# AzoreanReflowController.net
KiCad netlist of a schematic drawn in EAGLE
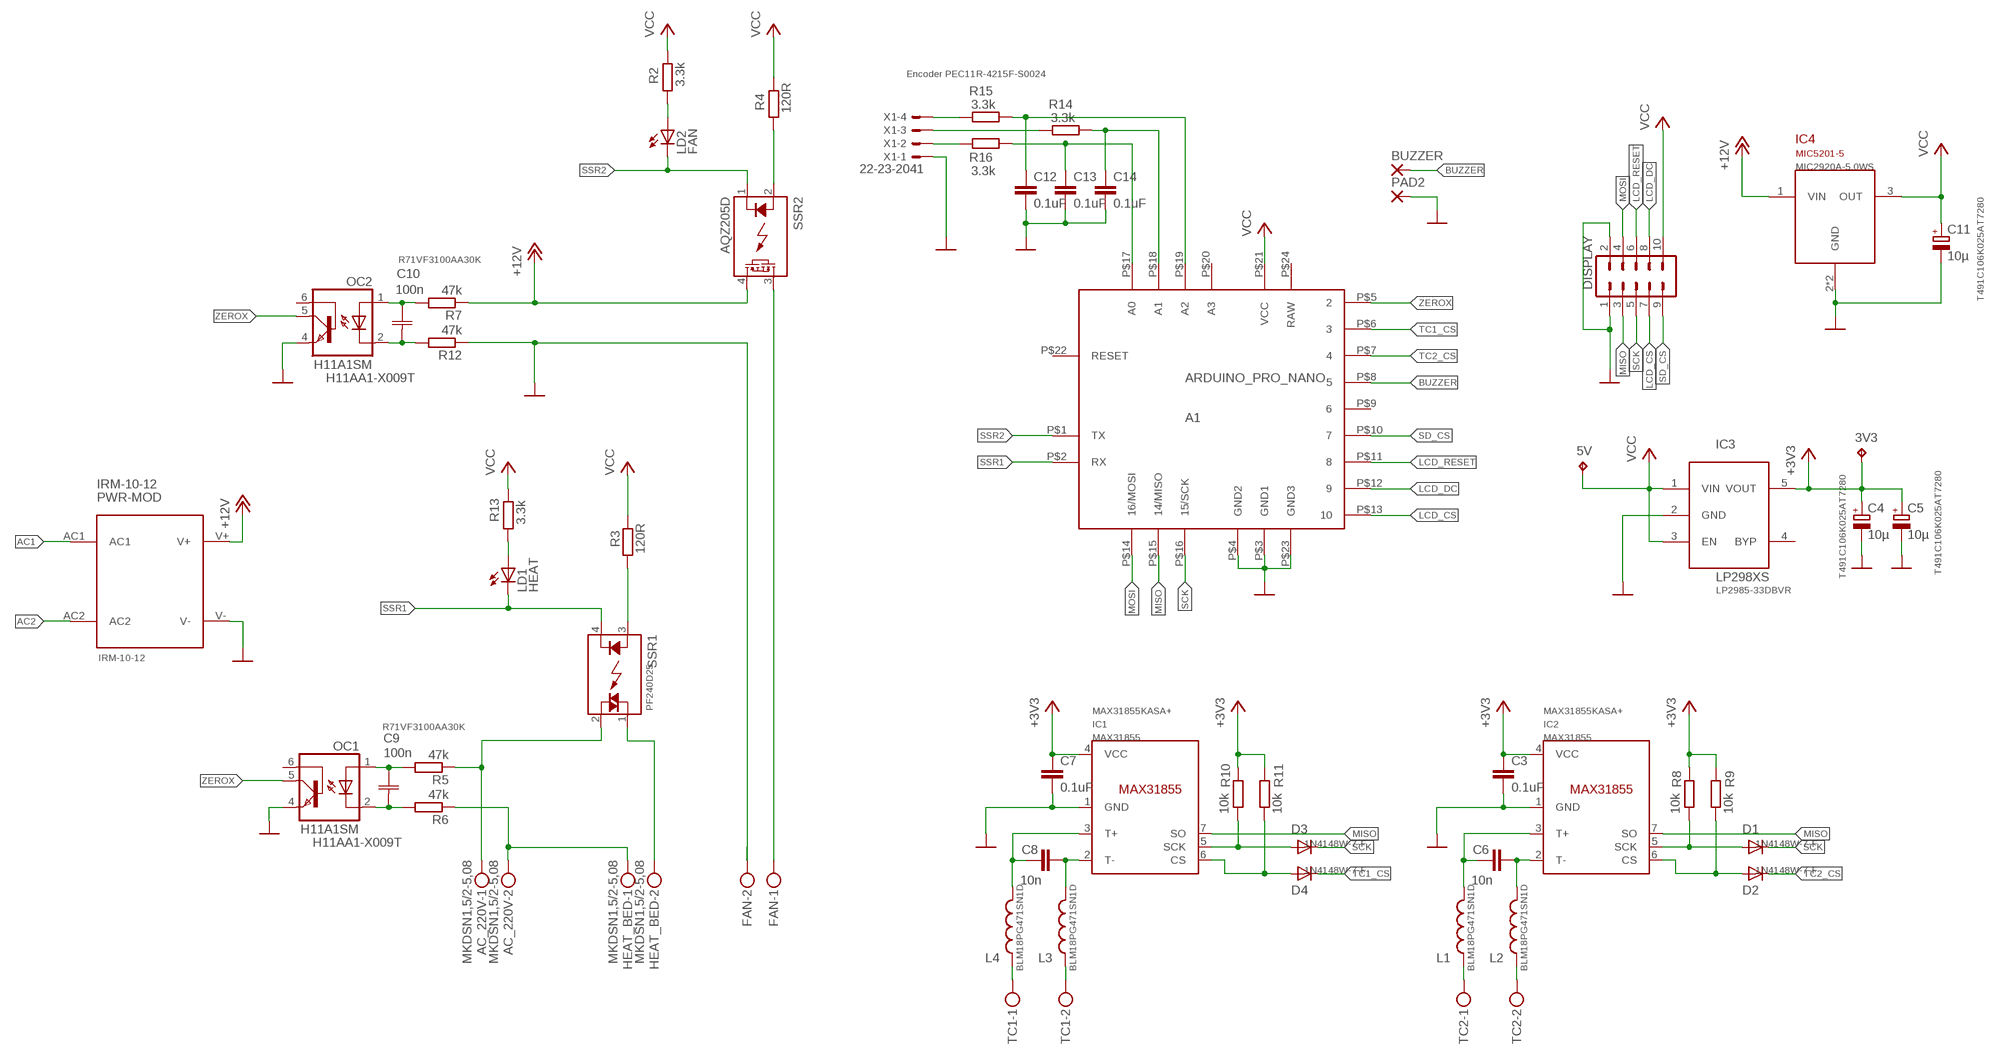
[diagram p0: schematic, sheet 1]

(export (version "E")
  (design (tool "Eeschema 10.0.6"))
  (components
    (comp (ref "3V3")
      (value "TPTP08R")
      (footprint "eagle-import:TP08R")
      (libsource (lib "eagle-import") (part "TPTP08R"))
    )
    (comp (ref "5V")
      (value "TPTP08R")
      (footprint "eagle-import:TP08R")
      (libsource (lib "eagle-import") (part "TPTP08R"))
    )
    (comp (ref "A1")
      (value "ARDUINO_PRO_NANO")
      (footprint "eagle-import:ARDUINO_PRO_NANO")
      (libsource (lib "eagle-import") (part "ARDUINO_PRO_NANO"))
    )
    (comp (ref "AC_220V")
      (value "MKDSN1,5/2-5,08")
      (footprint "eagle-import:MKDSN1,5_2-5,08")
      (fields (field (name "MPN") "MKDSN 1,5/2-5.08") (field (name "REF") "1715721 "))
      (libsource (lib "eagle-import") (part "MKDSN1,5/2-5,08"))
    )
    (comp (ref "BUZZER")
      (value "1,6/0,8")
      (footprint "eagle-import:1,6_0,8")
      (libsource (lib "eagle-import") (part "1,6/0,8"))
    )
    (comp (ref "C3")
      (value "0.1uF")
      (footprint "eagle-import:0603")
      (libsource (lib "eagle-import") (part "0.1UF-0603-25V-5%"))
    )
    (comp (ref "C4")
      (value "10µ")
      (footprint "eagle-import:C_6032-28R")
      (fields (field (name "REF") "T491C106K025AT7280"))
      (libsource (lib "eagle-import") (part "CPOL-EUC/6032-28R"))
    )
    (comp (ref "C5")
      (value "10µ")
      (footprint "eagle-import:C_6032-28R")
      (fields (field (name "REF") "T491C106K025AT7280"))
      (libsource (lib "eagle-import") (part "CPOL-EUC/6032-28R"))
    )
    (comp (ref "C6")
      (value "10n")
      (footprint "eagle-import:C0603")
      (libsource (lib "eagle-import") (part "C-EUC0603"))
    )
    (comp (ref "C7")
      (value "0.1uF")
      (footprint "eagle-import:0603")
      (libsource (lib "eagle-import") (part "0.1UF-0603-25V-5%"))
    )
    (comp (ref "C8")
      (value "10n")
      (footprint "eagle-import:C0603")
      (libsource (lib "eagle-import") (part "C-EUC0603"))
    )
    (comp (ref "C9")
      (value "100n")
      (footprint "eagle-import:R71V")
      (fields (field (name "REF") "R71VF3100AA30K"))
      (libsource (lib "eagle-import") (part "R71VF"))
    )
    (comp (ref "C10")
      (value "100n")
      (footprint "eagle-import:R71V")
      (fields (field (name "REF") "R71VF3100AA30K"))
      (libsource (lib "eagle-import") (part "R71VF"))
    )
    (comp (ref "C11")
      (value "10µ")
      (footprint "eagle-import:C_6032-28R")
      (fields (field (name "REF") "T491C106K025AT7280"))
      (libsource (lib "eagle-import") (part "CPOL-EUC/6032-28R"))
    )
    (comp (ref "C12")
      (value "0.1uF")
      (footprint "eagle-import:0603")
      (libsource (lib "eagle-import") (part "0.1UF-0603-25V-5%"))
    )
    (comp (ref "C13")
      (value "0.1uF")
      (footprint "eagle-import:0603")
      (libsource (lib "eagle-import") (part "0.1UF-0603-25V-5%"))
    )
    (comp (ref "C14")
      (value "0.1uF")
      (footprint "eagle-import:0603")
      (libsource (lib "eagle-import") (part "0.1UF-0603-25V-5%"))
    )
    (comp (ref "D1")
      (value "DIODESOD-123")
      (footprint "eagle-import:SOD-123")
      (fields (field (name "REF") "1N4148W-7-F"))
      (libsource (lib "eagle-import") (part "DIODESOD-123"))
    )
    (comp (ref "D2")
      (value "DIODESOD-123")
      (footprint "eagle-import:SOD-123")
      (fields (field (name "REF") "1N4148W-7-F"))
      (libsource (lib "eagle-import") (part "DIODESOD-123"))
    )
    (comp (ref "D3")
      (value "DIODESOD-123")
      (footprint "eagle-import:SOD-123")
      (fields (field (name "REF") "1N4148W-7-F"))
      (libsource (lib "eagle-import") (part "DIODESOD-123"))
    )
    (comp (ref "D4")
      (value "DIODESOD-123")
      (footprint "eagle-import:SOD-123")
      (fields (field (name "REF") "1N4148W-7-F"))
      (libsource (lib "eagle-import") (part "DIODESOD-123"))
    )
    (comp (ref "DISPLAY")
      (value "M05X2SHD-NS")
      (footprint "eagle-import:2X5-SHROUDED-NS")
      (libsource (lib "eagle-import") (part "M05X2SHD-NS"))
    )
    (comp (ref "FAN")
      (value "MKDSN1,5/2-5,08")
      (footprint "eagle-import:MKDSN1,5_2-5,08")
      (fields (field (name "MPN") "MKDSN 1,5/2-5.08") (field (name "REF") "1715721 "))
      (libsource (lib "eagle-import") (part "MKDSN1,5/2-5,08"))
    )
    (comp (ref "HEAT_BED")
      (value "MKDSN1,5/2-5,08")
      (footprint "eagle-import:MKDSN1,5_2-5,08")
      (fields (field (name "MPN") "MKDSN 1,5/2-5.08") (field (name "REF") "1715721 "))
      (libsource (lib "eagle-import") (part "MKDSN1,5/2-5,08"))
    )
    (comp (ref "IC1")
      (value "MAX31855")
      (footprint "eagle-import:SOIC8")
      (fields (field (name "REF") "MAX31855KASA+"))
      (libsource (lib "eagle-import") (part "MAX31855"))
    )
    (comp (ref "IC2")
      (value "MAX31855")
      (footprint "eagle-import:SOIC8")
      (fields (field (name "REF") "MAX31855KASA+"))
      (libsource (lib "eagle-import") (part "MAX31855"))
    )
    (comp (ref "IC3")
      (value "LP298XS")
      (footprint "eagle-import:SOT23-5L")
      (fields (field (name "REF") "LP2985-33DBVR"))
      (libsource (lib "eagle-import") (part "LP298XS"))
    )
    (comp (ref "IC4")
      (value "MIC5201-5")
      (footprint "eagle-import:SOT-223")
      (fields (field (name "REF") "MIC2920A-5.0WS"))
      (libsource (lib "eagle-import") (part "MIC5201-5"))
    )
    (comp (ref "L1")
      (value "INDUCTOR0603")
      (footprint "eagle-import:0603")
      (fields (field (name "REF") "BLM18PG471SN1D"))
      (libsource (lib "eagle-import") (part "INDUCTOR0603"))
    )
    (comp (ref "L2")
      (value "INDUCTOR0603")
      (footprint "eagle-import:0603")
      (fields (field (name "REF") "BLM18PG471SN1D"))
      (libsource (lib "eagle-import") (part "INDUCTOR0603"))
    )
    (comp (ref "L3")
      (value "INDUCTOR0603")
      (footprint "eagle-import:0603")
      (fields (field (name "REF") "BLM18PG471SN1D"))
      (libsource (lib "eagle-import") (part "INDUCTOR0603"))
    )
    (comp (ref "L4")
      (value "INDUCTOR0603")
      (footprint "eagle-import:0603")
      (fields (field (name "REF") "BLM18PG471SN1D"))
      (libsource (lib "eagle-import") (part "INDUCTOR0603"))
    )
    (comp (ref "LD1")
      (value "HEAT")
      (footprint "eagle-import:CHIP-LED0603")
      (libsource (lib "eagle-import") (part "LEDCHIP-LED0603"))
    )
    (comp (ref "LD2")
      (value "FAN")
      (footprint "eagle-import:CHIP-LED0603")
      (libsource (lib "eagle-import") (part "LEDCHIP-LED0603"))
    )
    (comp (ref "OC1")
      (value "H11A1SM")
      (footprint "eagle-import:DIL6-SMD")
      (fields (field (name "REF") "H11AA1-X009T"))
      (libsource (lib "eagle-import") (part "optocoupler_320_H11A?MS1"))
    )
    (comp (ref "OC2")
      (value "H11A1SM")
      (footprint "eagle-import:DIL6-SMD")
      (fields (field (name "REF") "H11AA1-X009T"))
      (libsource (lib "eagle-import") (part "H11A?MS1"))
    )
    (comp (ref "PAD2")
      (value "1,6/0,8")
      (footprint "eagle-import:1,6_0,8")
      (libsource (lib "eagle-import") (part "1,6/0,8"))
    )
    (comp (ref "PWR-MOD")
      (value "IRM-10-12")
      (footprint "eagle-import:IRM-10-12")
      (fields (field (name "REF") "IRM-10-12"))
      (libsource (lib "eagle-import") (part "IRM-10-12"))
    )
    (comp (ref "R2")
      (value "3.3k")
      (footprint "eagle-import:R0603")
      (libsource (lib "eagle-import") (part "R-EU_R0603"))
    )
    (comp (ref "R3")
      (value "120R")
      (footprint "eagle-import:R0603")
      (libsource (lib "eagle-import") (part "R-EU_R0603"))
    )
    (comp (ref "R4")
      (value "120R")
      (footprint "eagle-import:R0603")
      (libsource (lib "eagle-import") (part "R-EU_R0603"))
    )
    (comp (ref "R5")
      (value "47k")
      (footprint "eagle-import:0207_5V")
      (libsource (lib "eagle-import") (part "R-EU_0207/5V"))
    )
    (comp (ref "R6")
      (value "47k")
      (footprint "eagle-import:0207_5V")
      (libsource (lib "eagle-import") (part "R-EU_0207/5V"))
    )
    (comp (ref "R7")
      (value "47k")
      (footprint "eagle-import:0207_5V")
      (libsource (lib "eagle-import") (part "R-EU_0207/5V"))
    )
    (comp (ref "R8")
      (value "10k")
      (footprint "eagle-import:R0603")
      (libsource (lib "eagle-import") (part "R-EU_R0603"))
    )
    (comp (ref "R9")
      (value "10k")
      (footprint "eagle-import:R0603")
      (libsource (lib "eagle-import") (part "R-EU_R0603"))
    )
    (comp (ref "R10")
      (value "10k")
      (footprint "eagle-import:R0603")
      (libsource (lib "eagle-import") (part "R-EU_R0603"))
    )
    (comp (ref "R11")
      (value "10k")
      (footprint "eagle-import:R0603")
      (libsource (lib "eagle-import") (part "R-EU_R0603"))
    )
    (comp (ref "R12")
      (value "47k")
      (footprint "eagle-import:0207_5V")
      (libsource (lib "eagle-import") (part "R-EU_0207/5V"))
    )
    (comp (ref "R13")
      (value "3.3k")
      (footprint "eagle-import:R0603")
      (libsource (lib "eagle-import") (part "R-EU_R0603"))
    )
    (comp (ref "R14")
      (value "3.3k")
      (footprint "eagle-import:R0603")
      (libsource (lib "eagle-import") (part "R-EU_R0603"))
    )
    (comp (ref "R15")
      (value "3.3k")
      (footprint "eagle-import:R0603")
      (libsource (lib "eagle-import") (part "R-EU_R0603"))
    )
    (comp (ref "R16")
      (value "3.3k")
      (footprint "eagle-import:R0603")
      (libsource (lib "eagle-import") (part "R-EU_R0603"))
    )
    (comp (ref "SSR1")
      (value "PF240D25")
      (footprint "eagle-import:PF240XX")
      (fields (field (name "REF") "PF240D25"))
      (libsource (lib "eagle-import") (part "PF240D25"))
    )
    (comp (ref "SSR2")
      (value "AQZ205D")
      (footprint "eagle-import:AQZ-SIL04")
      (fields (field (name "MF") "AROMAT/ MATSUSHITA") (field (name "SPICEPREFIX") "K"))
      (libsource (lib "eagle-import") (part "AQZ20D5"))
    )
    (comp (ref "TC1")
      (value "MKDSN1,5/2-5,08")
      (footprint "eagle-import:MKDSN1,5_2-5,08")
      (fields (field (name "MPN") "MKDSN 1,5/2-5.08") (field (name "REF") "1715721 "))
      (libsource (lib "eagle-import") (part "MKDSN1,5/2-5,08"))
    )
    (comp (ref "TC2")
      (value "MKDSN1,5/2-5,08")
      (footprint "eagle-import:MKDSN1,5_2-5,08")
      (fields (field (name "MPN") "MKDSN 1,5/2-5.08") (field (name "REF") "1715721 "))
      (libsource (lib "eagle-import") (part "MKDSN1,5/2-5,08"))
    )
    (comp (ref "X1")
      (value "22-23-2041")
      (footprint "eagle-import:22-23-2041")
      (fields (field (name "MF") "MOLEX"))
      (libsource (lib "eagle-import") (part "22-23-2041"))
    )
  )
  (nets
    (net (code "1") (name "+3V3") (class "Default")
      (node (ref "3V3") (pin "TP") (pinfunction "TP_TP") (pintype "input"))
      (node (ref "C3") (pin "1") (pinfunction "1_1") (pintype "passive"))
      (node (ref "C4") (pin "+") (pinfunction "+_+") (pintype "passive"))
      (node (ref "C5") (pin "+") (pinfunction "+_+") (pintype "passive"))
      (node (ref "C7") (pin "1") (pinfunction "1_1") (pintype "passive"))
      (node (ref "IC1") (pin "4") (pinfunction "VCC_4") (pintype "power_in"))
      (node (ref "IC2") (pin "4") (pinfunction "VCC_4") (pintype "power_in"))
      (node (ref "IC3") (pin "5") (pinfunction "VOUT_5") (pintype "bidirectional"))
      (node (ref "R10") (pin "2") (pinfunction "2_2") (pintype "passive"))
      (node (ref "R11") (pin "2") (pinfunction "2_2") (pintype "passive"))
      (node (ref "R8") (pin "2") (pinfunction "2_2") (pintype "passive"))
      (node (ref "R9") (pin "2") (pinfunction "2_2") (pintype "passive"))
    )
    (net (code "2") (name "+12V") (class "Default")
      (node (ref "IC4") (pin "1") (pinfunction "VIN_1") (pintype "power_in"))
      (node (ref "PWR-MOD") (pin "V+") (pinfunction "V+_V+") (pintype "bidirectional"))
      (node (ref "R7") (pin "1") (pinfunction "1_1") (pintype "passive"))
      (node (ref "SSR2") (pin "4") (pinfunction "DS2_4") (pintype "passive"))
    )
    (net (code "3") (name "/RAW") (class "Default")
      (node (ref "A1") (pin "P$24") (pinfunction "RAW_P$24") (pintype "power_in"))
    )
    (net (code "4") (name "AC1") (class "Default")
      (node (ref "AC_220V") (pin "1") (pinfunction "KL_1") (pintype "passive"))
      (node (ref "PWR-MOD") (pin "AC1") (pinfunction "AC1_AC1") (pintype "bidirectional"))
      (node (ref "R5") (pin "1") (pinfunction "1_1") (pintype "passive"))
      (node (ref "SSR1") (pin "2") (pinfunction "ACL2_2") (pintype "passive"))
    )
    (net (code "5") (name "AC2") (class "Default")
      (node (ref "AC_220V") (pin "2") (pinfunction "KL_2") (pintype "passive"))
      (node (ref "HEAT_BED") (pin "1") (pinfunction "KL_1") (pintype "passive"))
      (node (ref "PWR-MOD") (pin "AC2") (pinfunction "AC2_AC2") (pintype "bidirectional"))
      (node (ref "R6") (pin "1") (pinfunction "1_1") (pintype "passive"))
    )
    (net (code "6") (name "BUZZER") (class "Default")
      (node (ref "A1") (pin "P$8") (pinfunction "5_P$8") (pintype "bidirectional"))
      (node (ref "BUZZER") (pin "1") (pinfunction "P_1") (pintype "passive"))
    )
    (net (code "7") (name "GND") (class "Default")
      (node (ref "A1") (pin "P$23") (pinfunction "GND3_P$23") (pintype "power_in"))
      (node (ref "A1") (pin "P$3") (pinfunction "GND1_P$3") (pintype "power_in"))
      (node (ref "A1") (pin "P$4") (pinfunction "GND2_P$4") (pintype "power_in"))
      (node (ref "C11") (pin "-") (pinfunction "-_-") (pintype "passive"))
      (node (ref "C12") (pin "2") (pinfunction "2_2") (pintype "passive"))
      (node (ref "C13") (pin "2") (pinfunction "2_2") (pintype "passive"))
      (node (ref "C14") (pin "2") (pinfunction "2_2") (pintype "passive"))
      (node (ref "C3") (pin "2") (pinfunction "2_2") (pintype "passive"))
      (node (ref "C4") (pin "-") (pinfunction "-_-") (pintype "passive"))
      (node (ref "C5") (pin "-") (pinfunction "-_-") (pintype "passive"))
      (node (ref "C7") (pin "2") (pinfunction "2_2") (pintype "passive"))
      (node (ref "DISPLAY") (pin "1") (pinfunction "1_1") (pintype "passive"))
      (node (ref "DISPLAY") (pin "2") (pinfunction "2_2") (pintype "passive"))
      (node (ref "FAN") (pin "2") (pinfunction "KL_2") (pintype "passive"))
      (node (ref "IC1") (pin "1") (pinfunction "GND_1") (pintype "power_in"))
      (node (ref "IC2") (pin "1") (pinfunction "GND_1") (pintype "power_in"))
      (node (ref "IC3") (pin "2") (pinfunction "GND_2") (pintype "bidirectional"))
      (node (ref "IC4") (pin "2") (pinfunction "GND_2") (pintype "power_in"))
      (node (ref "IC4") (pin "4") (pinfunction "GND_4") (pintype "power_in"))
      (node (ref "OC1") (pin "4") (pinfunction "EMI_4") (pintype "passive"))
      (node (ref "OC2") (pin "4") (pinfunction "EMI_4") (pintype "passive"))
      (node (ref "PAD2") (pin "1") (pinfunction "P_1") (pintype "passive"))
      (node (ref "PWR-MOD") (pin "V-") (pinfunction "V-_V-") (pintype "bidirectional"))
      (node (ref "R12") (pin "1") (pinfunction "1_1") (pintype "passive"))
      (node (ref "X1") (pin "1") (pinfunction "S_1") (pintype "passive"))
    )
    (net (code "8") (name "LCD_CS") (class "Default")
      (node (ref "A1") (pin "P$13") (pinfunction "10_P$13") (pintype "bidirectional"))
      (node (ref "DISPLAY") (pin "7") (pinfunction "7_7") (pintype "passive"))
    )
    (net (code "9") (name "LCD_DC") (class "Default")
      (node (ref "A1") (pin "P$12") (pinfunction "9_P$12") (pintype "bidirectional"))
      (node (ref "DISPLAY") (pin "8") (pinfunction "8_8") (pintype "passive"))
    )
    (net (code "10") (name "LCD_RESET") (class "Default")
      (node (ref "A1") (pin "P$11") (pinfunction "8_P$11") (pintype "bidirectional"))
      (node (ref "DISPLAY") (pin "6") (pinfunction "6_6") (pintype "passive"))
    )
    (net (code "11") (name "MISO") (class "Default")
      (node (ref "A1") (pin "P$15") (pinfunction "14/MISO_P$15") (pintype "bidirectional"))
      (node (ref "DISPLAY") (pin "3") (pinfunction "3_3") (pintype "passive"))
      (node (ref "IC1") (pin "7") (pinfunction "SO_7") (pintype "output"))
      (node (ref "IC2") (pin "7") (pinfunction "SO_7") (pintype "output"))
    )
    (net (code "12") (name "MOSI") (class "Default")
      (node (ref "A1") (pin "P$14") (pinfunction "16/MOSI_P$14") (pintype "bidirectional"))
      (node (ref "DISPLAY") (pin "4") (pinfunction "4_4") (pintype "passive"))
    )
    (net (code "13") (name "Net-(A1-A0)") (class "Default")
      (node (ref "A1") (pin "P$17") (pinfunction "A0_P$17") (pintype "bidirectional"))
      (node (ref "C13") (pin "1") (pinfunction "1_1") (pintype "passive"))
      (node (ref "R16") (pin "2") (pinfunction "2_2") (pintype "passive"))
    )
    (net (code "14") (name "Net-(A1-A1)") (class "Default")
      (node (ref "A1") (pin "P$18") (pinfunction "A1_P$18") (pintype "bidirectional"))
      (node (ref "C14") (pin "1") (pinfunction "1_1") (pintype "passive"))
      (node (ref "R14") (pin "2") (pinfunction "2_2") (pintype "passive"))
    )
    (net (code "15") (name "Net-(A1-A2)") (class "Default")
      (node (ref "A1") (pin "P$19") (pinfunction "A2_P$19") (pintype "bidirectional"))
      (node (ref "C12") (pin "1") (pinfunction "1_1") (pintype "passive"))
      (node (ref "R15") (pin "2") (pinfunction "2_2") (pintype "passive"))
    )
    (net (code "16") (name "Net-(FANA-KL)") (class "Default")
      (node (ref "FAN") (pin "1") (pinfunction "KL_1") (pintype "passive"))
      (node (ref "SSR2") (pin "3") (pinfunction "DS1_3") (pintype "passive"))
    )
    (net (code "17") (name "Net-(HEAT_BEDB-KL)") (class "Default")
      (node (ref "HEAT_BED") (pin "2") (pinfunction "KL_2") (pintype "passive"))
      (node (ref "SSR1") (pin "1") (pinfunction "ACL1_1") (pintype "passive"))
    )
    (net (code "18") (name "Net-(IC1-CS)") (class "Default")
      (node (ref "D4") (pin "A") (pinfunction "A_A") (pintype "passive"))
      (node (ref "IC1") (pin "6") (pinfunction "CS_6") (pintype "input"))
      (node (ref "R11") (pin "1") (pinfunction "1_1") (pintype "passive"))
    )
    (net (code "19") (name "Net-(IC1-SCK)") (class "Default")
      (node (ref "D3") (pin "A") (pinfunction "A_A") (pintype "passive"))
      (node (ref "IC1") (pin "5") (pinfunction "SCK_5") (pintype "input"))
      (node (ref "R10") (pin "1") (pinfunction "1_1") (pintype "passive"))
    )
    (net (code "20") (name "Net-(IC1-T+)") (class "Default")
      (node (ref "C8") (pin "1") (pinfunction "1_1") (pintype "passive"))
      (node (ref "IC1") (pin "3") (pinfunction "T+_3") (pintype "input"))
      (node (ref "L4") (pin "2") (pinfunction "2_2") (pintype "passive"))
    )
    (net (code "21") (name "Net-(IC1-T-)") (class "Default")
      (node (ref "C8") (pin "2") (pinfunction "2_2") (pintype "passive"))
      (node (ref "IC1") (pin "2") (pinfunction "T-_2") (pintype "input"))
      (node (ref "L3") (pin "2") (pinfunction "2_2") (pintype "passive"))
    )
    (net (code "22") (name "Net-(IC2-CS)") (class "Default")
      (node (ref "D2") (pin "A") (pinfunction "A_A") (pintype "passive"))
      (node (ref "IC2") (pin "6") (pinfunction "CS_6") (pintype "input"))
      (node (ref "R9") (pin "1") (pinfunction "1_1") (pintype "passive"))
    )
    (net (code "23") (name "Net-(IC2-SCK)") (class "Default")
      (node (ref "D1") (pin "A") (pinfunction "A_A") (pintype "passive"))
      (node (ref "IC2") (pin "5") (pinfunction "SCK_5") (pintype "input"))
      (node (ref "R8") (pin "1") (pinfunction "1_1") (pintype "passive"))
    )
    (net (code "24") (name "Net-(IC2-T+)") (class "Default")
      (node (ref "C6") (pin "1") (pinfunction "1_1") (pintype "passive"))
      (node (ref "IC2") (pin "3") (pinfunction "T+_3") (pintype "input"))
      (node (ref "L1") (pin "2") (pinfunction "2_2") (pintype "passive"))
    )
    (net (code "25") (name "Net-(IC2-T-)") (class "Default")
      (node (ref "C6") (pin "2") (pinfunction "2_2") (pintype "passive"))
      (node (ref "IC2") (pin "2") (pinfunction "T-_2") (pintype "input"))
      (node (ref "L2") (pin "2") (pinfunction "2_2") (pintype "passive"))
    )
    (net (code "26") (name "Net-(LD1-PadA)") (class "Default")
      (node (ref "LD1") (pin "A") (pinfunction "A_A") (pintype "passive"))
      (node (ref "R13") (pin "2") (pinfunction "2_2") (pintype "passive"))
    )
    (net (code "27") (name "Net-(LD2-PadA)") (class "Default")
      (node (ref "LD2") (pin "A") (pinfunction "A_A") (pintype "passive"))
      (node (ref "R2") (pin "2") (pinfunction "2_2") (pintype "passive"))
    )
    (net (code "28") (name "Net-(OC1-A)") (class "Default")
      (node (ref "C9") (pin "1") (pinfunction "1_1") (pintype "passive"))
      (node (ref "OC1") (pin "1") (pinfunction "A_1") (pintype "passive"))
      (node (ref "R5") (pin "2") (pinfunction "2_2") (pintype "passive"))
    )
    (net (code "29") (name "Net-(OC1-C)") (class "Default")
      (node (ref "C9") (pin "2") (pinfunction "2_2") (pintype "passive"))
      (node (ref "OC1") (pin "2") (pinfunction "C_2") (pintype "passive"))
      (node (ref "R6") (pin "2") (pinfunction "2_2") (pintype "passive"))
    )
    (net (code "30") (name "Net-(OC2-A)") (class "Default")
      (node (ref "C10") (pin "1") (pinfunction "1_1") (pintype "passive"))
      (node (ref "OC2") (pin "1") (pinfunction "A_1") (pintype "passive"))
      (node (ref "R7") (pin "2") (pinfunction "2_2") (pintype "passive"))
    )
    (net (code "31") (name "Net-(OC2-C)") (class "Default")
      (node (ref "C10") (pin "2") (pinfunction "2_2") (pintype "passive"))
      (node (ref "OC2") (pin "2") (pinfunction "C_2") (pintype "passive"))
      (node (ref "R12") (pin "2") (pinfunction "2_2") (pintype "passive"))
    )
    (net (code "32") (name "Net-(SSR1-DC+)") (class "Default")
      (node (ref "R3") (pin "2") (pinfunction "2_2") (pintype "passive"))
      (node (ref "SSR1") (pin "3") (pinfunction "DC+_3") (pintype "passive"))
    )
    (net (code "33") (name "Net-(SSR2-A)") (class "Default")
      (node (ref "R4") (pin "2") (pinfunction "2_2") (pintype "passive"))
      (node (ref "SSR2") (pin "2") (pinfunction "A_2") (pintype "passive"))
    )
    (net (code "34") (name "Net-(TC1A-KL)") (class "Default")
      (node (ref "L4") (pin "1") (pinfunction "1_1") (pintype "passive"))
      (node (ref "TC1") (pin "1") (pinfunction "KL_1") (pintype "passive"))
    )
    (net (code "35") (name "Net-(TC1B-KL)") (class "Default")
      (node (ref "L3") (pin "1") (pinfunction "1_1") (pintype "passive"))
      (node (ref "TC1") (pin "2") (pinfunction "KL_2") (pintype "passive"))
    )
    (net (code "36") (name "Net-(TC2A-KL)") (class "Default")
      (node (ref "L1") (pin "1") (pinfunction "1_1") (pintype "passive"))
      (node (ref "TC2") (pin "1") (pinfunction "KL_1") (pintype "passive"))
    )
    (net (code "37") (name "Net-(TC2B-KL)") (class "Default")
      (node (ref "L2") (pin "1") (pinfunction "1_1") (pintype "passive"))
      (node (ref "TC2") (pin "2") (pinfunction "KL_2") (pintype "passive"))
    )
    (net (code "38") (name "Net-(X1B-S)") (class "Default")
      (node (ref "R16") (pin "1") (pinfunction "1_1") (pintype "passive"))
      (node (ref "X1") (pin "2") (pinfunction "S_2") (pintype "passive"))
    )
    (net (code "39") (name "Net-(X1C-S)") (class "Default")
      (node (ref "R14") (pin "1") (pinfunction "1_1") (pintype "passive"))
      (node (ref "X1") (pin "3") (pinfunction "S_3") (pintype "passive"))
    )
    (net (code "40") (name "Net-(X1D-S)") (class "Default")
      (node (ref "R15") (pin "1") (pinfunction "1_1") (pintype "passive"))
      (node (ref "X1") (pin "4") (pinfunction "S_4") (pintype "passive"))
    )
    (net (code "41") (name "SCK") (class "Default")
      (node (ref "A1") (pin "P$16") (pinfunction "15/SCK_P$16") (pintype "bidirectional"))
      (node (ref "D1") (pin "C") (pinfunction "C_C") (pintype "passive"))
      (node (ref "D3") (pin "C") (pinfunction "C_C") (pintype "passive"))
      (node (ref "DISPLAY") (pin "5") (pinfunction "5_5") (pintype "passive"))
    )
    (net (code "42") (name "SD_CS") (class "Default")
      (node (ref "A1") (pin "P$10") (pinfunction "7_P$10") (pintype "bidirectional"))
      (node (ref "DISPLAY") (pin "9") (pinfunction "9_9") (pintype "passive"))
    )
    (net (code "43") (name "SSR1") (class "Default")
      (node (ref "A1") (pin "P$2") (pinfunction "RX_P$2") (pintype "bidirectional"))
      (node (ref "LD1") (pin "C") (pinfunction "C_C") (pintype "passive"))
      (node (ref "SSR1") (pin "4") (pinfunction "DC-_4") (pintype "passive"))
    )
    (net (code "44") (name "SSR2") (class "Default")
      (node (ref "A1") (pin "P$1") (pinfunction "TX_P$1") (pintype "bidirectional"))
      (node (ref "LD2") (pin "C") (pinfunction "C_C") (pintype "passive"))
      (node (ref "SSR2") (pin "1") (pinfunction "K_1") (pintype "passive"))
    )
    (net (code "45") (name "TC1_CS") (class "Default")
      (node (ref "A1") (pin "P$6") (pinfunction "3_P$6") (pintype "bidirectional"))
      (node (ref "D4") (pin "C") (pinfunction "C_C") (pintype "passive"))
    )
    (net (code "46") (name "TC2_CS") (class "Default")
      (node (ref "A1") (pin "P$7") (pinfunction "4_P$7") (pintype "bidirectional"))
      (node (ref "D2") (pin "C") (pinfunction "C_C") (pintype "passive"))
    )
    (net (code "47") (name "VCC") (class "Default")
      (node (ref "5V") (pin "TP") (pinfunction "TP_TP") (pintype "input"))
      (node (ref "A1") (pin "P$21") (pinfunction "VCC_P$21") (pintype "power_in"))
      (node (ref "C11") (pin "+") (pinfunction "+_+") (pintype "passive"))
      (node (ref "DISPLAY") (pin "10") (pinfunction "10_10") (pintype "passive"))
      (node (ref "IC3") (pin "1") (pinfunction "VIN_1") (pintype "bidirectional"))
      (node (ref "IC3") (pin "3") (pinfunction "EN_3") (pintype "bidirectional"))
      (node (ref "IC4") (pin "3") (pinfunction "OUT_3") (pintype "output"))
      (node (ref "R13") (pin "1") (pinfunction "1_1") (pintype "passive"))
      (node (ref "R2") (pin "1") (pinfunction "1_1") (pintype "passive"))
      (node (ref "R3") (pin "1") (pinfunction "1_1") (pintype "passive"))
      (node (ref "R4") (pin "1") (pinfunction "1_1") (pintype "passive"))
    )
    (net (code "48") (name "ZEROX") (class "Default")
      (node (ref "A1") (pin "P$5") (pinfunction "2_P$5") (pintype "bidirectional"))
      (node (ref "OC1") (pin "5") (pinfunction "COL_5") (pintype "passive"))
      (node (ref "OC2") (pin "5") (pinfunction "COL_5") (pintype "passive"))
    )
    (net (code "49") (name "unconnected-(A1-6-PadP$9)") (class "Default")
      (node (ref "A1") (pin "P$9") (pinfunction "6_P$9") (pintype "bidirectional"))
    )
    (net (code "50") (name "unconnected-(A1-A3-PadP$20)") (class "Default")
      (node (ref "A1") (pin "P$20") (pinfunction "A3_P$20") (pintype "bidirectional"))
    )
    (net (code "51") (name "unconnected-(A1-RESET-PadP$22)") (class "Default")
      (node (ref "A1") (pin "P$22") (pinfunction "RESET_P$22") (pintype "bidirectional"))
    )
    (net (code "52") (name "unconnected-(IC3-BYP-Pad4)") (class "Default")
      (node (ref "IC3") (pin "4") (pinfunction "BYP_4") (pintype "bidirectional"))
    )
    (net (code "53") (name "unconnected-(OC1-BAS-Pad6)") (class "Default")
      (node (ref "OC1") (pin "6") (pinfunction "BAS_6") (pintype "passive"))
    )
    (net (code "54") (name "unconnected-(OC2-BAS-Pad6)") (class "Default")
      (node (ref "OC2") (pin "6") (pinfunction "BAS_6") (pintype "passive"))
    )
  )
)
